# Sensor_Screen.net
KiCad netlist of a schematic drawn in Altium Designer
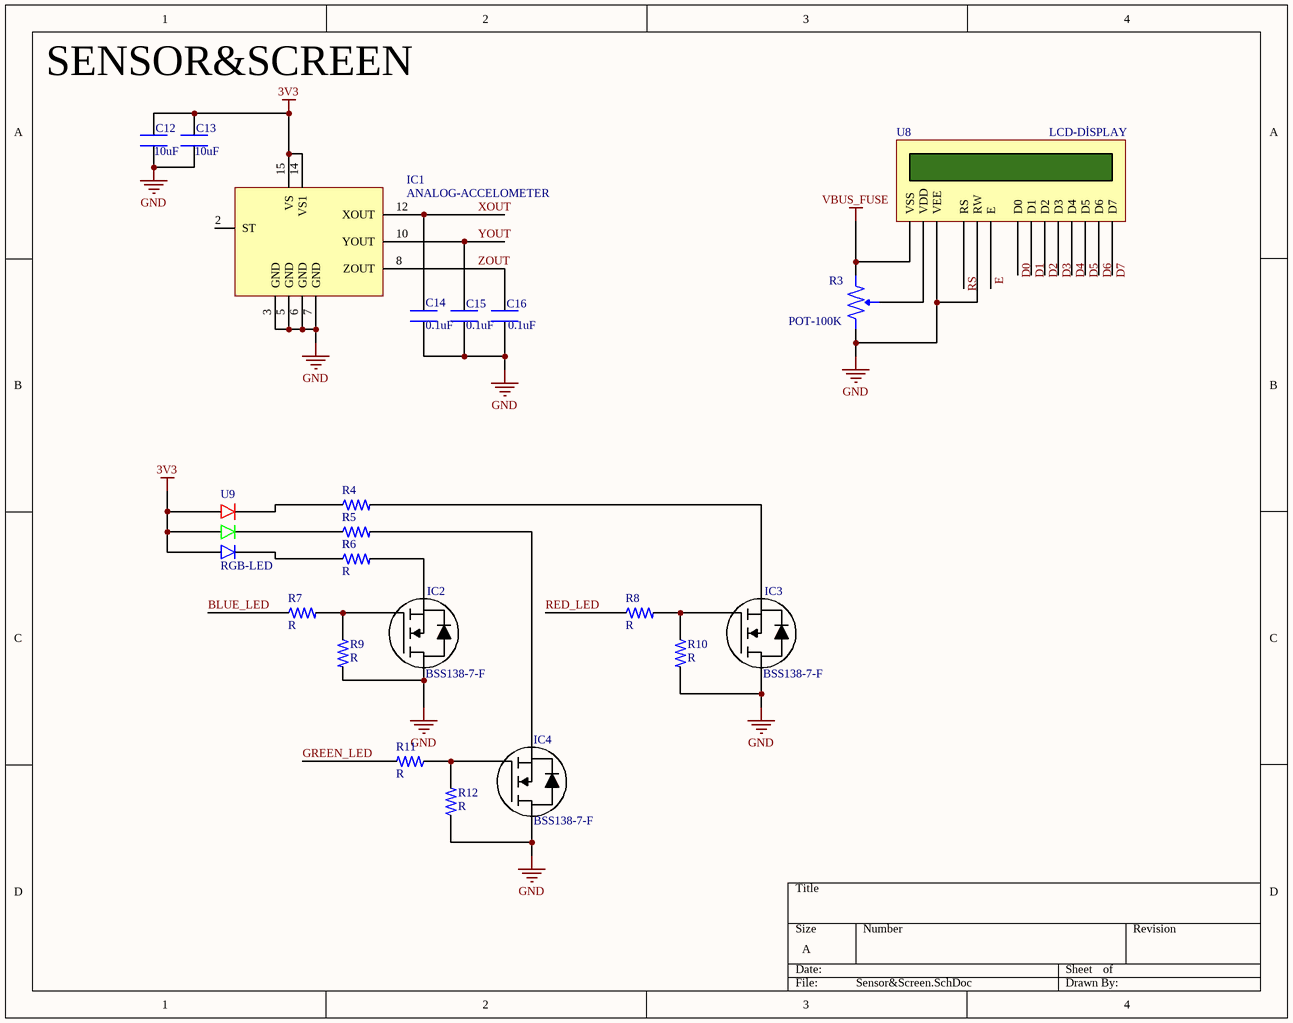
[diagram p0: Sensor&Screen.SchDoc]

(export (version "E")
  (design (tool "Eeschema 10.0.6"))
  (components
    (comp (ref "C12")
      (value "10uF")
      (footprint "capacitor-1206:PCBComponent_1")
      (libsource (lib "capacitor-1206") (part "1206-CAPACİTOR"))
    )
    (comp (ref "C13")
      (value "10uF")
      (footprint "capacitor-1206:PCBComponent_1")
      (libsource (lib "capacitor-1206") (part "1206-CAPACİTOR"))
    )
    (comp (ref "C14")
      (value "0.1uF")
      (footprint "capacitor-1206:PCBComponent_1")
      (libsource (lib "capacitor-1206") (part "1206-CAPACİTOR"))
    )
    (comp (ref "C15")
      (value "0.1uF")
      (footprint "capacitor-1206:PCBComponent_1")
      (libsource (lib "capacitor-1206") (part "1206-CAPACİTOR"))
    )
    (comp (ref "C16")
      (value "0.1uF")
      (footprint "capacitor-1206:PCBComponent_1")
      (libsource (lib "capacitor-1206") (part "1206-CAPACİTOR"))
    )
    (comp (ref "IC1")
      (value "ANALOG-ACCELOMETER")
      (footprint "ADXL335:PCBComponent_1")
      (libsource (lib "ADXL33X") (part "ADXL33X"))
    )
    (comp (ref "IC2")
      (value "BSS138-7-F")
      (footprint "MOSFET-N-Channel:PCBComponent_1")
      (libsource (lib "MOSFET-N-Channel") (part "Component_1"))
    )
    (comp (ref "IC3")
      (value "BSS138-7-F")
      (footprint "MOSFET-N-Channel:PCBComponent_1")
      (libsource (lib "MOSFET-N-Channel") (part "Component_1"))
    )
    (comp (ref "IC4")
      (value "BSS138-7-F")
      (footprint "MOSFET-N-Channel:PCBComponent_1")
      (libsource (lib "MOSFET-N-Channel") (part "Component_1"))
    )
    (comp (ref "R3")
      (value "POT-100K")
      (footprint "POT-100K:PCBComponent_1")
      (libsource (lib "POT") (part "L-KLS4-R0902N-B100K-L25-"))
    )
    (comp (ref "R4")
      (value "R")
      (footprint "1206-Resistor:PCBComponent_1")
      (libsource (lib "1206-Resistor") (part "1206-RESİSTOR"))
    )
    (comp (ref "R5")
      (value "R")
      (footprint "1206-Resistor:PCBComponent_1")
      (libsource (lib "1206-Resistor") (part "1206-RESİSTOR"))
    )
    (comp (ref "R6")
      (value "R")
      (footprint "1206-Resistor:PCBComponent_1")
      (libsource (lib "1206-Resistor") (part "1206-RESİSTOR"))
    )
    (comp (ref "R7")
      (value "R")
      (footprint "1206-Resistor:PCBComponent_1")
      (libsource (lib "1206-Resistor") (part "1206-RESİSTOR"))
    )
    (comp (ref "R8")
      (value "R")
      (footprint "1206-Resistor:PCBComponent_1")
      (libsource (lib "1206-Resistor") (part "1206-RESİSTOR"))
    )
    (comp (ref "R9")
      (value "R")
      (footprint "1206-Resistor:PCBComponent_1")
      (libsource (lib "1206-Resistor") (part "1206-RESİSTOR"))
    )
    (comp (ref "R10")
      (value "R")
      (footprint "1206-Resistor:PCBComponent_1")
      (libsource (lib "1206-Resistor") (part "1206-RESİSTOR"))
    )
    (comp (ref "R11")
      (value "R")
      (footprint "1206-Resistor:PCBComponent_1")
      (libsource (lib "1206-Resistor") (part "1206-RESİSTOR"))
    )
    (comp (ref "R12")
      (value "R")
      (footprint "1206-Resistor:PCBComponent_1")
      (libsource (lib "1206-Resistor") (part "1206-RESİSTOR"))
    )
    (comp (ref "U8")
      (value "LCD-DİSPLAY")
      (footprint "LCD0802A:PCBComponent_1")
      (libsource (lib "LCD0802A") (part "0802A"))
    )
    (comp (ref "U9")
      (value "RGB-LED")
      (footprint "RGB-SMD-5050-LED:PCBComponent_1")
      (libsource (lib "RGB-SMD-5050-LED") (part "FYLS-5050NRGB"))
    )
  )
  (nets
    (net (code "1") (name "/BLUE_LED") (class "Default")
      (node (ref "R7") (pin "1") (pinfunction "1_1") (pintype "passive"))
    )
    (net (code "2") (name "/D0") (class "Default")
      (node (ref "U8") (pin "7") (pinfunction "D0_7") (pintype "passive"))
    )
    (net (code "3") (name "/D1") (class "Default")
      (node (ref "U8") (pin "8") (pinfunction "D1_8") (pintype "passive"))
    )
    (net (code "4") (name "/D2") (class "Default")
      (node (ref "U8") (pin "9") (pinfunction "D2_9") (pintype "passive"))
    )
    (net (code "5") (name "/D3") (class "Default")
      (node (ref "U8") (pin "10") (pinfunction "D3_10") (pintype "passive"))
    )
    (net (code "6") (name "/D4") (class "Default")
      (node (ref "U8") (pin "11") (pinfunction "D4_11") (pintype "passive"))
    )
    (net (code "7") (name "/D5") (class "Default")
      (node (ref "U8") (pin "12") (pinfunction "D5_12") (pintype "passive"))
    )
    (net (code "8") (name "/D6") (class "Default")
      (node (ref "U8") (pin "13") (pinfunction "D6_13") (pintype "passive"))
    )
    (net (code "9") (name "/D7") (class "Default")
      (node (ref "U8") (pin "14") (pinfunction "D7_14") (pintype "passive"))
    )
    (net (code "10") (name "/E") (class "Default")
      (node (ref "U8") (pin "6") (pinfunction "E_6") (pintype "passive"))
    )
    (net (code "11") (name "/GREEN_LED") (class "Default")
      (node (ref "R11") (pin "2") (pinfunction "2_2") (pintype "passive"))
    )
    (net (code "12") (name "/RED_LED") (class "Default")
      (node (ref "R8") (pin "1") (pinfunction "1_1") (pintype "passive"))
    )
    (net (code "13") (name "/RS") (class "Default")
      (node (ref "U8") (pin "4") (pinfunction "RS_4") (pintype "passive"))
    )
    (net (code "14") (name "/XOUT") (class "Default")
      (node (ref "C14") (pin "2") (pinfunction "2_2") (pintype "passive"))
      (node (ref "IC1") (pin "12") (pinfunction "XOUT_12") (pintype "passive"))
    )
    (net (code "15") (name "/YOUT") (class "Default")
      (node (ref "C15") (pin "2") (pinfunction "2_2") (pintype "passive"))
      (node (ref "IC1") (pin "10") (pinfunction "YOUT_10") (pintype "passive"))
    )
    (net (code "16") (name "/ZOUT") (class "Default")
      (node (ref "C16") (pin "2") (pinfunction "2_2") (pintype "passive"))
      (node (ref "IC1") (pin "8") (pinfunction "ZOUT_8") (pintype "passive"))
    )
    (net (code "17") (name "3V3") (class "Default")
      (node (ref "C12") (pin "2") (pinfunction "2_2") (pintype "passive"))
      (node (ref "C13") (pin "2") (pinfunction "2_2") (pintype "passive"))
      (node (ref "IC1") (pin "14") (pinfunction "VS1_14") (pintype "passive"))
      (node (ref "IC1") (pin "15") (pinfunction "VS_15") (pintype "passive"))
      (node (ref "U9") (pin "4") (pinfunction "R_4") (pintype "passive"))
      (node (ref "U9") (pin "5") (pinfunction "G_5") (pintype "passive"))
      (node (ref "U9") (pin "6") (pinfunction "B_6") (pintype "passive"))
    )
    (net (code "18") (name "GND") (class "Default")
      (node (ref "C12") (pin "1") (pinfunction "1_1") (pintype "passive"))
      (node (ref "C13") (pin "1") (pinfunction "1_1") (pintype "passive"))
      (node (ref "C14") (pin "1") (pinfunction "1_1") (pintype "passive"))
      (node (ref "C15") (pin "1") (pinfunction "1_1") (pintype "passive"))
      (node (ref "C16") (pin "1") (pinfunction "1_1") (pintype "passive"))
      (node (ref "IC1") (pin "3") (pinfunction "GND_3") (pintype "passive"))
      (node (ref "IC1") (pin "5") (pinfunction "GND_5") (pintype "passive"))
      (node (ref "IC1") (pin "6") (pinfunction "GND_6") (pintype "passive"))
      (node (ref "IC1") (pin "7") (pinfunction "GND_7") (pintype "passive"))
      (node (ref "IC2") (pin "3") (pinfunction "SOURCE_3") (pintype "passive"))
      (node (ref "IC3") (pin "3") (pinfunction "SOURCE_3") (pintype "passive"))
      (node (ref "IC4") (pin "3") (pinfunction "SOURCE_3") (pintype "passive"))
      (node (ref "R10") (pin "2") (pinfunction "2_2") (pintype "passive"))
      (node (ref "R12") (pin "1") (pinfunction "1_1") (pintype "passive"))
      (node (ref "R3") (pin "3") (pintype "passive"))
      (node (ref "R9") (pin "2") (pinfunction "2_2") (pintype "passive"))
      (node (ref "U8") (pin "3") (pinfunction "VEE_3") (pintype "passive"))
      (node (ref "U8") (pin "5") (pinfunction "RW_5") (pintype "passive"))
    )
    (net (code "19") (name "Net-(IC2-DRAİN)") (class "Default")
      (node (ref "IC2") (pin "2") (pinfunction "DRAİN_2") (pintype "passive"))
      (node (ref "R6") (pin "2") (pinfunction "2_2") (pintype "passive"))
    )
    (net (code "20") (name "Net-(IC2-GATE)") (class "Default")
      (node (ref "IC2") (pin "1") (pinfunction "GATE_1") (pintype "passive"))
      (node (ref "R7") (pin "2") (pinfunction "2_2") (pintype "passive"))
      (node (ref "R9") (pin "1") (pinfunction "1_1") (pintype "passive"))
    )
    (net (code "21") (name "Net-(IC3-DRAİN)") (class "Default")
      (node (ref "IC3") (pin "2") (pinfunction "DRAİN_2") (pintype "passive"))
      (node (ref "R4") (pin "2") (pinfunction "2_2") (pintype "passive"))
    )
    (net (code "22") (name "Net-(IC3-GATE)") (class "Default")
      (node (ref "IC3") (pin "1") (pinfunction "GATE_1") (pintype "passive"))
      (node (ref "R10") (pin "1") (pinfunction "1_1") (pintype "passive"))
      (node (ref "R8") (pin "2") (pinfunction "2_2") (pintype "passive"))
    )
    (net (code "23") (name "Net-(IC4-DRAİN)") (class "Default")
      (node (ref "IC4") (pin "2") (pinfunction "DRAİN_2") (pintype "passive"))
      (node (ref "R5") (pin "2") (pinfunction "2_2") (pintype "passive"))
    )
    (net (code "24") (name "Net-(IC4-GATE)") (class "Default")
      (node (ref "IC4") (pin "1") (pinfunction "GATE_1") (pintype "passive"))
      (node (ref "R11") (pin "1") (pinfunction "1_1") (pintype "passive"))
      (node (ref "R12") (pin "2") (pinfunction "2_2") (pintype "passive"))
    )
    (net (code "25") (name "Net-(R4-Pad1)") (class "Default")
      (node (ref "R4") (pin "1") (pinfunction "1_1") (pintype "passive"))
      (node (ref "U9") (pin "3") (pintype "passive"))
    )
    (net (code "26") (name "Net-(R5-Pad1)") (class "Default")
      (node (ref "R5") (pin "1") (pinfunction "1_1") (pintype "passive"))
      (node (ref "U9") (pin "2") (pintype "passive"))
    )
    (net (code "27") (name "Net-(R6-Pad1)") (class "Default")
      (node (ref "R6") (pin "1") (pinfunction "1_1") (pintype "passive"))
      (node (ref "U9") (pin "1") (pintype "passive"))
    )
    (net (code "28") (name "Net-(U8-VDD)") (class "Default")
      (node (ref "R3") (pin "2") (pintype "passive"))
      (node (ref "U8") (pin "2") (pinfunction "VDD_2") (pintype "passive"))
    )
    (net (code "29") (name "VBUS_FUSE") (class "Default")
      (node (ref "R3") (pin "1") (pintype "passive"))
      (node (ref "U8") (pin "1") (pinfunction "VSS_1") (pintype "passive"))
    )
    (net (code "30") (name "unconnected-(IC1-ST-Pad2)") (class "Default")
      (node (ref "IC1") (pin "2") (pinfunction "ST_2") (pintype "passive"))
    )
  )
)
